# DisplayCarrier.net
KiCad netlist of a schematic drawn in EAGLE
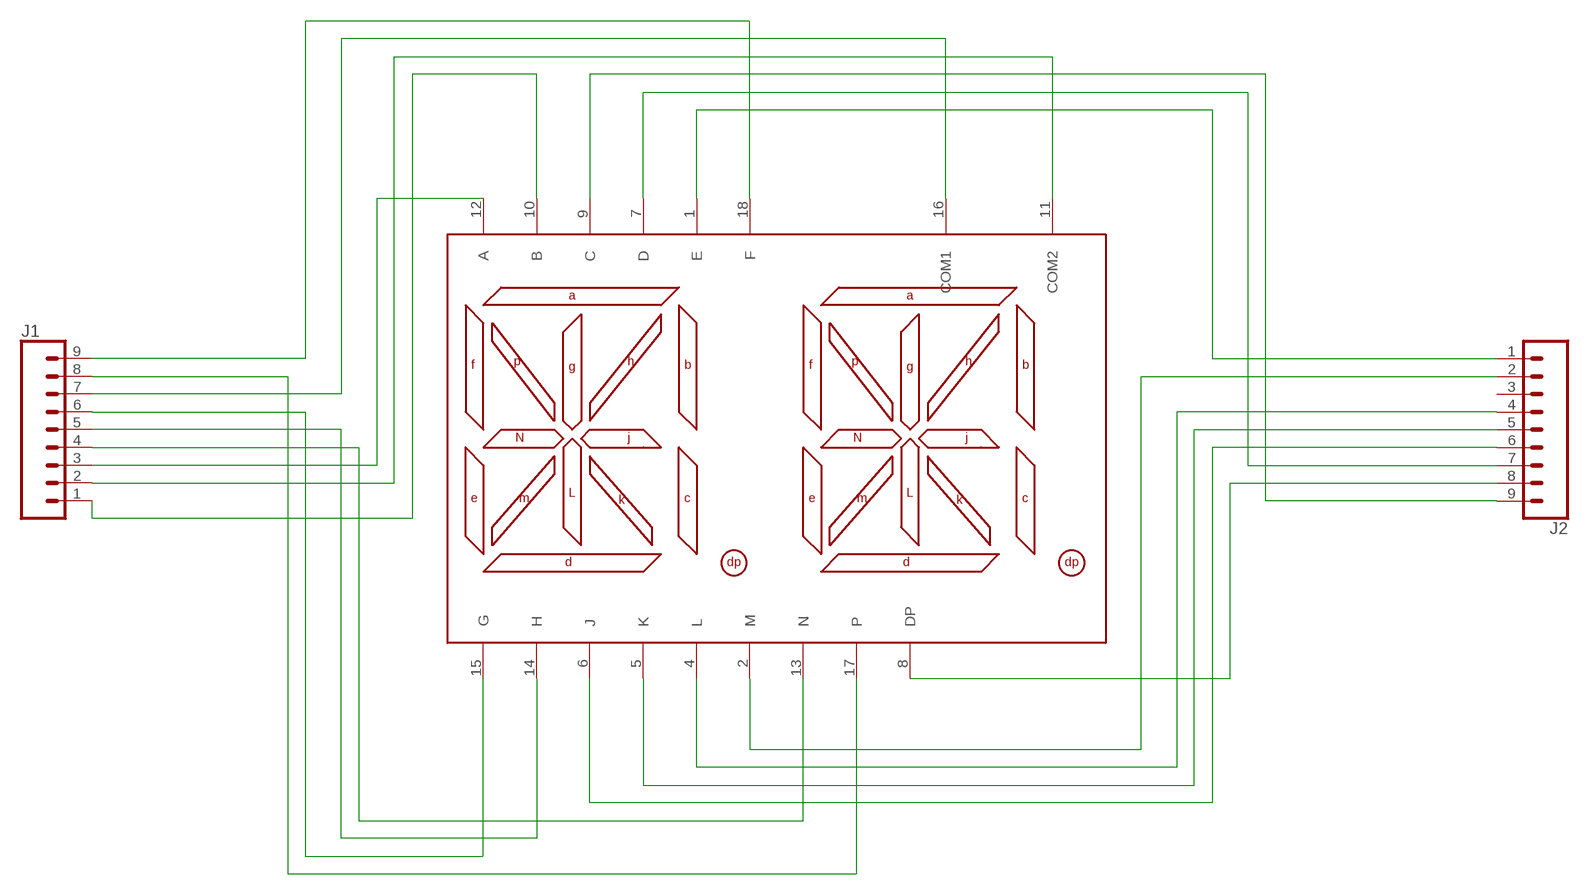
[diagram p0: schematic, sheet 1]

(export (version "E")
  (design (tool "Eeschema 10.0.6"))
  (components
    (comp (ref "J1")
      (value "CONN_09")
      (footprint "eagle-import:1X09")
      (libsource (lib "eagle-import") (part "CONN_09"))
    )
    (comp (ref "J2")
      (value "CONN_09")
      (footprint "eagle-import:1X09")
      (libsource (lib "eagle-import") (part "CONN_09"))
    )
    (comp (ref "U$1")
      (value "HDSP-A27C")
      (footprint "eagle-import:DIP-18")
      (libsource (lib "eagle-import") (part "HDSP-A27C"))
    )
  )
  (nets
    (net (code "1") (name "Net-(U$1-A)") (class "Default")
      (node (ref "J1") (pin "3") (pinfunction "3_3") (pintype "passive"))
      (node (ref "U$1") (pin "12") (pinfunction "A_12") (pintype "bidirectional"))
    )
    (net (code "2") (name "Net-(U$1-B)") (class "Default")
      (node (ref "J1") (pin "1") (pinfunction "1_1") (pintype "passive"))
      (node (ref "U$1") (pin "10") (pinfunction "B_10") (pintype "bidirectional"))
    )
    (net (code "3") (name "Net-(U$1-C)") (class "Default")
      (node (ref "J2") (pin "9") (pinfunction "9_9") (pintype "passive"))
      (node (ref "U$1") (pin "9") (pinfunction "C_9") (pintype "bidirectional"))
    )
    (net (code "4") (name "Net-(U$1-COM1)") (class "Default")
      (node (ref "J1") (pin "7") (pinfunction "7_7") (pintype "passive"))
      (node (ref "U$1") (pin "16") (pinfunction "COM1_16") (pintype "bidirectional"))
    )
    (net (code "5") (name "Net-(U$1-COM2)") (class "Default")
      (node (ref "J1") (pin "2") (pinfunction "2_2") (pintype "passive"))
      (node (ref "U$1") (pin "11") (pinfunction "COM2_11") (pintype "bidirectional"))
    )
    (net (code "6") (name "Net-(U$1-D)") (class "Default")
      (node (ref "J2") (pin "7") (pinfunction "7_7") (pintype "passive"))
      (node (ref "U$1") (pin "7") (pinfunction "D_7") (pintype "bidirectional"))
    )
    (net (code "7") (name "Net-(U$1-DP)") (class "Default")
      (node (ref "J2") (pin "8") (pinfunction "8_8") (pintype "passive"))
      (node (ref "U$1") (pin "8") (pinfunction "DP_8") (pintype "bidirectional"))
    )
    (net (code "8") (name "Net-(U$1-E)") (class "Default")
      (node (ref "J2") (pin "1") (pinfunction "1_1") (pintype "passive"))
      (node (ref "U$1") (pin "1") (pinfunction "E_1") (pintype "bidirectional"))
    )
    (net (code "9") (name "Net-(U$1-F)") (class "Default")
      (node (ref "J1") (pin "9") (pinfunction "9_9") (pintype "passive"))
      (node (ref "U$1") (pin "18") (pinfunction "F_18") (pintype "bidirectional"))
    )
    (net (code "10") (name "Net-(U$1-G)") (class "Default")
      (node (ref "J1") (pin "6") (pinfunction "6_6") (pintype "passive"))
      (node (ref "U$1") (pin "15") (pinfunction "G_15") (pintype "bidirectional"))
    )
    (net (code "11") (name "Net-(U$1-H)") (class "Default")
      (node (ref "J1") (pin "5") (pinfunction "5_5") (pintype "passive"))
      (node (ref "U$1") (pin "14") (pinfunction "H_14") (pintype "bidirectional"))
    )
    (net (code "12") (name "Net-(U$1-J)") (class "Default")
      (node (ref "J2") (pin "6") (pinfunction "6_6") (pintype "passive"))
      (node (ref "U$1") (pin "6") (pinfunction "J_6") (pintype "bidirectional"))
    )
    (net (code "13") (name "Net-(U$1-K)") (class "Default")
      (node (ref "J2") (pin "5") (pinfunction "5_5") (pintype "passive"))
      (node (ref "U$1") (pin "5") (pinfunction "K_5") (pintype "bidirectional"))
    )
    (net (code "14") (name "Net-(U$1-L)") (class "Default")
      (node (ref "J2") (pin "4") (pinfunction "4_4") (pintype "passive"))
      (node (ref "U$1") (pin "4") (pinfunction "L_4") (pintype "bidirectional"))
    )
    (net (code "15") (name "Net-(U$1-M)") (class "Default")
      (node (ref "J2") (pin "2") (pinfunction "2_2") (pintype "passive"))
      (node (ref "U$1") (pin "2") (pinfunction "M_2") (pintype "bidirectional"))
    )
    (net (code "16") (name "Net-(U$1-N)") (class "Default")
      (node (ref "J1") (pin "4") (pinfunction "4_4") (pintype "passive"))
      (node (ref "U$1") (pin "13") (pinfunction "N_13") (pintype "bidirectional"))
    )
    (net (code "17") (name "Net-(U$1-P)") (class "Default")
      (node (ref "J1") (pin "8") (pinfunction "8_8") (pintype "passive"))
      (node (ref "U$1") (pin "17") (pinfunction "P_17") (pintype "bidirectional"))
    )
    (net (code "18") (name "unconnected-(J2-Pad3)") (class "Default")
      (node (ref "J2") (pin "3") (pinfunction "3_3") (pintype "passive"))
    )
  )
)
